# Zio_LiPo_Battery_Manager.net
KiCad netlist of a schematic drawn in EAGLE
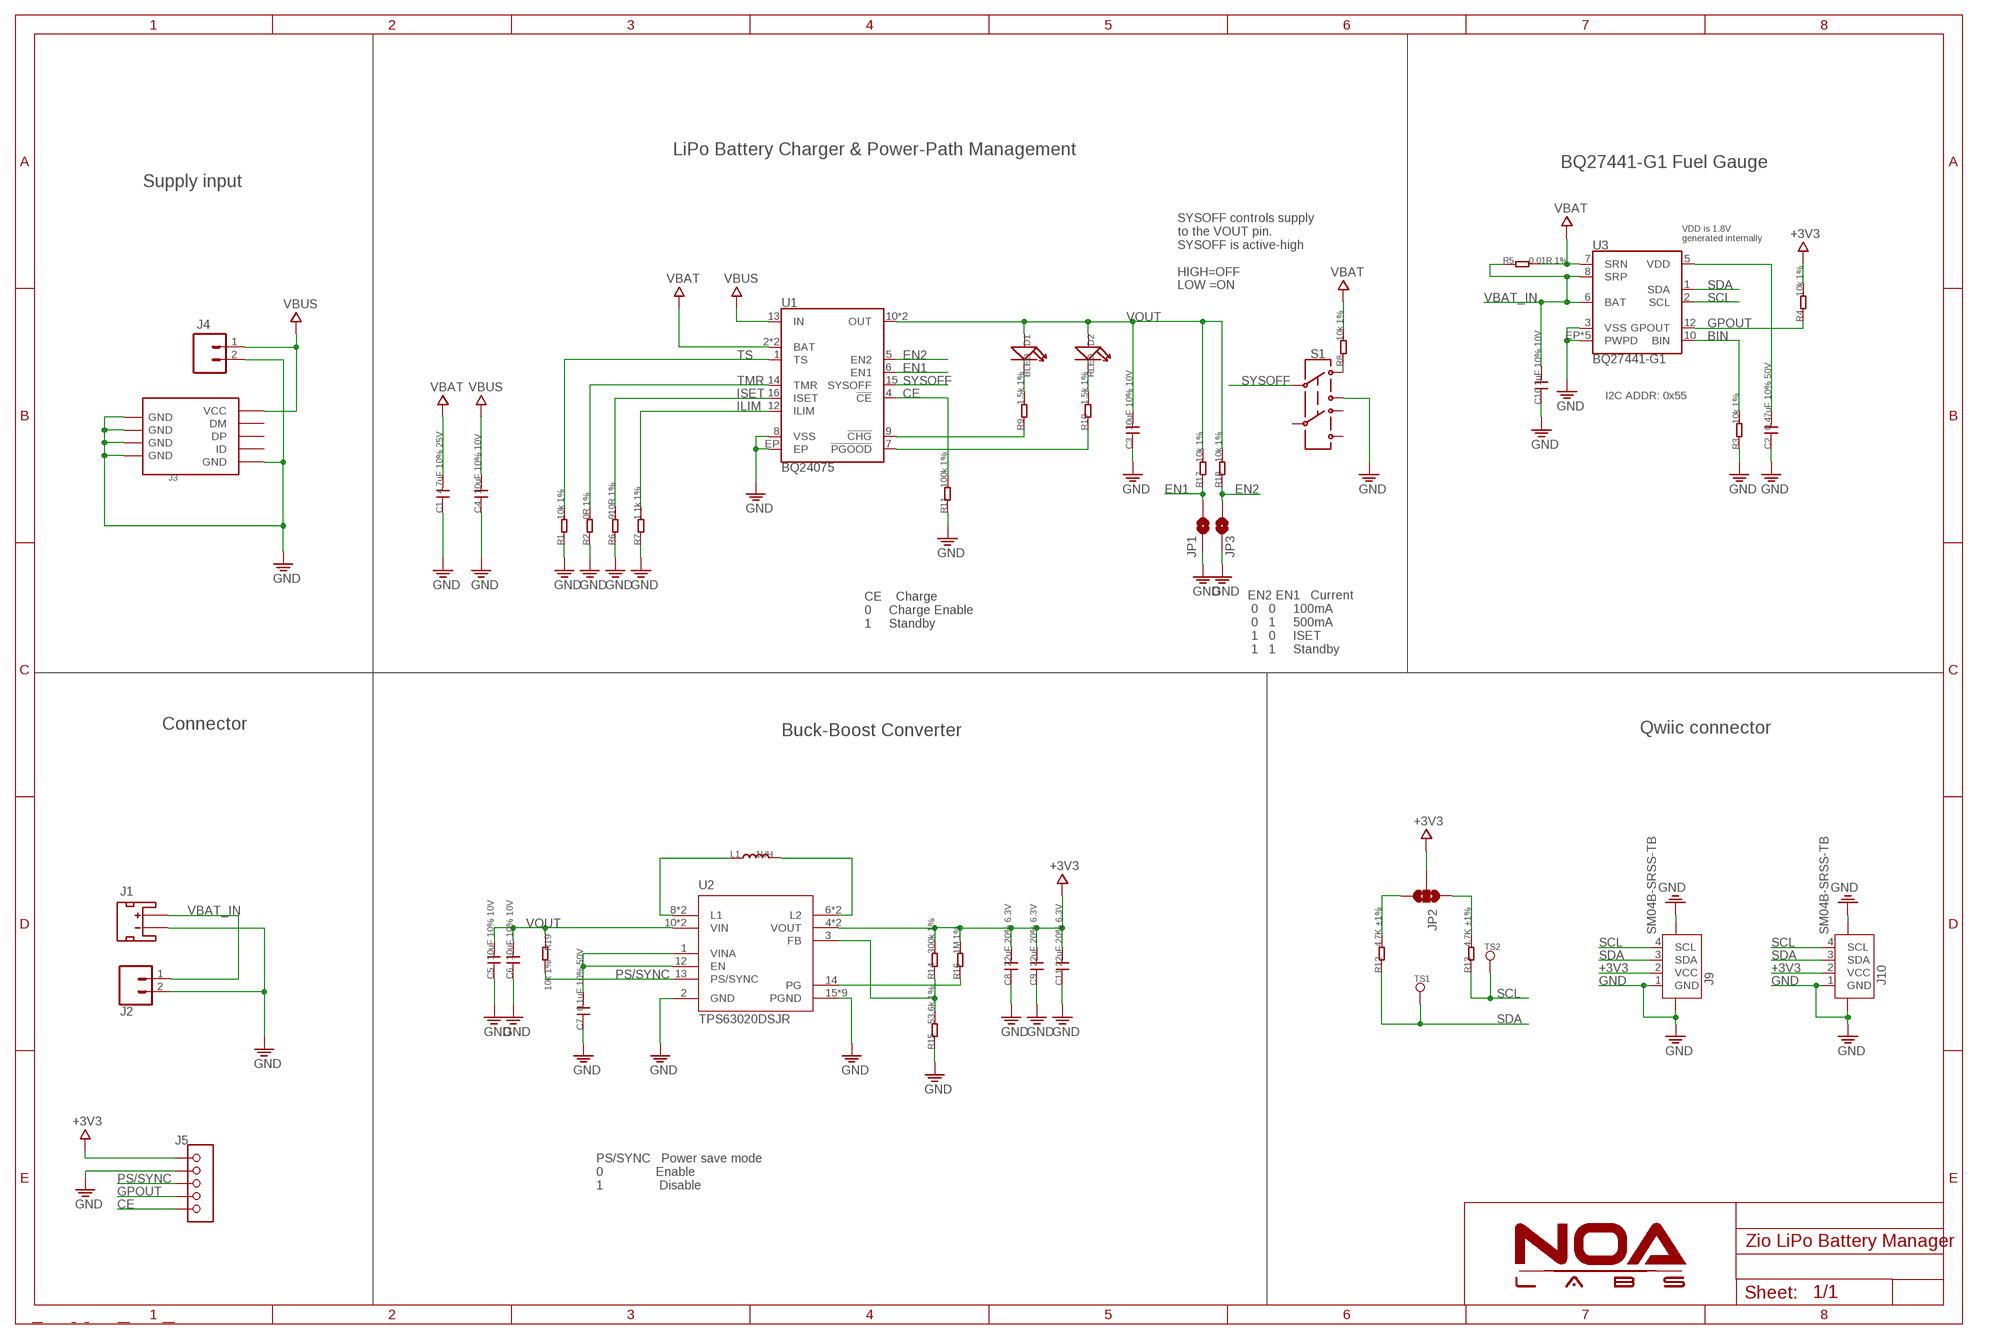
[diagram p0: schematic, sheet 1]

(export (version "E")
  (design (tool "Eeschema 10.0.6"))
  (components
    (comp (ref "C1")
      (value "4.7uF 10% 25V")
      (footprint "eagle-import:0603")
      (libsource (lib "eagle-import") (part "C-0603"))
    )
    (comp (ref "C2")
      (value "0.47uF 10% 50V")
      (footprint "eagle-import:0603")
      (libsource (lib "eagle-import") (part "C-0603"))
    )
    (comp (ref "C3")
      (value "10uF 10% 10V")
      (footprint "eagle-import:0805")
      (libsource (lib "eagle-import") (part "C-0805"))
    )
    (comp (ref "C4")
      (value "10uF 10% 10V")
      (footprint "eagle-import:0805")
      (libsource (lib "eagle-import") (part "C-0805"))
    )
    (comp (ref "C5")
      (value "10uF 10% 10V")
      (footprint "eagle-import:0805")
      (libsource (lib "eagle-import") (part "C-0805"))
    )
    (comp (ref "C6")
      (value "10uF 10% 10V")
      (footprint "eagle-import:0805")
      (libsource (lib "eagle-import") (part "C-0805"))
    )
    (comp (ref "C7")
      (value "0.1uF 10% 50V")
      (footprint "eagle-import:0603")
      (libsource (lib "eagle-import") (part "C-0603"))
    )
    (comp (ref "C8")
      (value "22uF 20% 6.3V")
      (footprint "eagle-import:0805")
      (libsource (lib "eagle-import") (part "C-0805"))
    )
    (comp (ref "C9")
      (value "22uF 20% 6.3V")
      (footprint "eagle-import:0805")
      (libsource (lib "eagle-import") (part "C-0805"))
    )
    (comp (ref "C10")
      (value "1uF 10% 10V")
      (footprint "eagle-import:0603")
      (libsource (lib "eagle-import") (part "C-0603"))
    )
    (comp (ref "C11")
      (value "22uF 20% 6.3V")
      (footprint "eagle-import:0805")
      (libsource (lib "eagle-import") (part "C-0805"))
    )
    (comp (ref "D1")
      (value "BLED")
      (footprint "eagle-import:LED-0603")
      (libsource (lib "eagle-import") (part "LED'0603'"))
    )
    (comp (ref "D2")
      (value "RLED")
      (footprint "eagle-import:LED-0603")
      (libsource (lib "eagle-import") (part "LED'0603'"))
    )
    (comp (ref "J1")
      (value "JST_2MM_MALE")
      (footprint "eagle-import:JST-2-SMD")
      (libsource (lib "eagle-import") (part "JST_2MM_MALE"))
    )
    (comp (ref "J2")
      (value "CONN_02")
      (footprint "eagle-import:1X02")
      (libsource (lib "eagle-import") (part "CONN_02"))
    )
    (comp (ref "J3")
      (value "USB-MICROE")
      (footprint "eagle-import:MICRO-SMD")
      (libsource (lib "eagle-import") (part "USB-MICROE"))
    )
    (comp (ref "J4")
      (value "CONN_02")
      (footprint "eagle-import:1X02")
      (libsource (lib "eagle-import") (part "CONN_02"))
    )
    (comp (ref "J5")
      (value "HEADER-5P-2.54")
      (footprint "eagle-import:5P-2.54")
      (libsource (lib "eagle-import") (part "HEADER-5P-2.54"))
    )
    (comp (ref "J9")
      (value "SM04B-SRSS-TB")
      (footprint "eagle-import:JST-SH-4P")
      (libsource (lib "eagle-import") (part "JST-SH-4P-1.0"))
    )
    (comp (ref "J10")
      (value "SM04B-SRSS-TB")
      (footprint "eagle-import:JST-SH-4P")
      (libsource (lib "eagle-import") (part "JST-SH-4P-1.0"))
    )
    (comp (ref "JP1")
      (value "JUMPER-SMT_2_NC_PASTE_NOCREM")
      (footprint "eagle-import:SMT-JUMPER_2_NC_PASTE_SILK_NOCREM")
      (libsource (lib "eagle-import") (part "JUMPER-SMT_2_NC_PASTE_NOCREM"))
    )
    (comp (ref "JP2")
      (value "JUMPER-SMT_3_2-NC_PASTE_NOCREM")
      (footprint "eagle-import:SMT-JUMPER_3_2-NC_PASTE_SILK_NOCREM")
      (libsource (lib "eagle-import") (part "JUMPER-SMT_3_2-NC_PASTE_NOCREM"))
    )
    (comp (ref "JP3")
      (value "JUMPER-SMT_2_NC_PASTE_NOCREM")
      (footprint "eagle-import:SMT-JUMPER_2_NC_PASTE_SILK_NOCREM")
      (libsource (lib "eagle-import") (part "JUMPER-SMT_2_NC_PASTE_NOCREM"))
    )
    (comp (ref "L1")
      (value "1UH")
      (footprint "eagle-import:0420M")
      (libsource (lib "eagle-import") (part "L-0420M"))
    )
    (comp (ref "R1")
      (value "10k 1%")
      (footprint "eagle-import:0603")
      (libsource (lib "eagle-import") (part "R-0603"))
    )
    (comp (ref "R2")
      (value "0R 1%")
      (footprint "eagle-import:0603")
      (libsource (lib "eagle-import") (part "R-0603"))
    )
    (comp (ref "R3")
      (value "10k 1%")
      (footprint "eagle-import:0603")
      (libsource (lib "eagle-import") (part "R-0603"))
    )
    (comp (ref "R4")
      (value "10k 1%")
      (footprint "eagle-import:0603")
      (libsource (lib "eagle-import") (part "R-0603"))
    )
    (comp (ref "R5")
      (value "0.01R 1%")
      (footprint "eagle-import:1206")
      (libsource (lib "eagle-import") (part "R-1206"))
    )
    (comp (ref "R6")
      (value "910R 1%")
      (footprint "eagle-import:0603")
      (libsource (lib "eagle-import") (part "R-0603"))
    )
    (comp (ref "R7")
      (value "1.1k 1%")
      (footprint "eagle-import:0603")
      (libsource (lib "eagle-import") (part "R-0603"))
    )
    (comp (ref "R8")
      (value "10k 1%")
      (footprint "eagle-import:0603")
      (libsource (lib "eagle-import") (part "R-0603"))
    )
    (comp (ref "R9")
      (value "1.5k 1%")
      (footprint "eagle-import:0603")
      (libsource (lib "eagle-import") (part "R-0603"))
    )
    (comp (ref "R10")
      (value "1.5k 1%")
      (footprint "eagle-import:0603")
      (libsource (lib "eagle-import") (part "R-0603"))
    )
    (comp (ref "R11")
      (value "100k 1%")
      (footprint "eagle-import:0603")
      (libsource (lib "eagle-import") (part "R-0603"))
    )
    (comp (ref "R12")
      (value "4.7K ±1%")
      (footprint "eagle-import:0603")
      (libsource (lib "eagle-import") (part "R-0603"))
    )
    (comp (ref "R13")
      (value "4.7K ±1%")
      (footprint "eagle-import:0603")
      (libsource (lib "eagle-import") (part "R-0603"))
    )
    (comp (ref "R14")
      (value "300k 1%")
      (footprint "eagle-import:0603")
      (libsource (lib "eagle-import") (part "R-0603"))
    )
    (comp (ref "R15")
      (value "53.6k 1%")
      (footprint "eagle-import:0603")
      (libsource (lib "eagle-import") (part "R-0603"))
    )
    (comp (ref "R16")
      (value "1M 1%")
      (footprint "eagle-import:0603")
      (libsource (lib "eagle-import") (part "R-0603"))
    )
    (comp (ref "R17")
      (value "10k 1%")
      (footprint "eagle-import:0603")
      (libsource (lib "eagle-import") (part "R-0603"))
    )
    (comp (ref "R18")
      (value "10k 1%")
      (footprint "eagle-import:0603")
      (libsource (lib "eagle-import") (part "R-0603"))
    )
    (comp (ref "R19")
      (value "10k 1%")
      (footprint "eagle-import:0603")
      (libsource (lib "eagle-import") (part "R-0603"))
    )
    (comp (ref "S1")
      (value "SWITCH-DPDT-SMD-AYZ0202")
      (footprint "eagle-import:SWITCH_DPDT_SMD_AYZ0202")
      (libsource (lib "eagle-import") (part "SWITCH-DPDT-SMD-AYZ0202"))
    )
    (comp (ref "TS1")
      (value "TEST_POINT35MIL")
      (footprint "eagle-import:1P-35MIL")
      (libsource (lib "eagle-import") (part "TEST_POINT35MIL"))
    )
    (comp (ref "TS2")
      (value "TEST_POINT35MIL")
      (footprint "eagle-import:1P-35MIL")
      (libsource (lib "eagle-import") (part "TEST_POINT35MIL"))
    )
    (comp (ref "U1")
      (value "BQ24075")
      (footprint "eagle-import:PVQFN-N16")
      (libsource (lib "eagle-import") (part "BQ24075"))
    )
    (comp (ref "U2")
      (value "TPS63020DSJR")
      (footprint "eagle-import:VSON-14")
      (libsource (lib "eagle-import") (part "TPS63020DSJR"))
    )
    (comp (ref "U3")
      (value "BQ27441-G1")
      (footprint "eagle-import:PDSO-N12")
      (libsource (lib "eagle-import") (part "BQ27441-G1"))
    )
  )
  (nets
    (net (code "1") (name "+3V3") (class "Default")
      (node (ref "C11") (pin "2") (pinfunction "2_2") (pintype "passive"))
      (node (ref "C8") (pin "2") (pinfunction "2_2") (pintype "passive"))
      (node (ref "C9") (pin "2") (pinfunction "2_2") (pintype "passive"))
      (node (ref "J10") (pin "2") (pinfunction "VCC_2") (pintype "bidirectional"))
      (node (ref "J5") (pin "1") (pinfunction "1_1") (pintype "bidirectional"))
      (node (ref "J9") (pin "2") (pinfunction "VCC_2") (pintype "bidirectional"))
      (node (ref "JP2") (pin "2") (pinfunction "2_2") (pintype "passive"))
      (node (ref "R14") (pin "2") (pinfunction "2_2") (pintype "passive"))
      (node (ref "R16") (pin "2") (pinfunction "2_2") (pintype "passive"))
      (node (ref "R4") (pin "2") (pinfunction "2_2") (pintype "passive"))
      (node (ref "U2") (pin "4") (pinfunction "VOUT_4") (pintype "bidirectional"))
      (node (ref "U2") (pin "5") (pinfunction "VOUT_5") (pintype "bidirectional"))
    )
    (net (code "2") (name "/BIN") (class "Default")
      (node (ref "R3") (pin "2") (pinfunction "2_2") (pintype "passive"))
      (node (ref "U3") (pin "10") (pinfunction "BIN_10") (pintype "bidirectional"))
    )
    (net (code "3") (name "/CE") (class "Default")
      (node (ref "J5") (pin "5") (pinfunction "5_5") (pintype "bidirectional"))
      (node (ref "R11") (pin "2") (pinfunction "2_2") (pintype "passive"))
      (node (ref "U1") (pin "4") (pinfunction "~{CE}_4") (pintype "bidirectional"))
    )
    (net (code "4") (name "/EN1") (class "Default")
      (node (ref "JP1") (pin "2") (pinfunction "2_2") (pintype "passive"))
      (node (ref "R17") (pin "1") (pinfunction "1_1") (pintype "passive"))
      (node (ref "U1") (pin "6") (pinfunction "EN1_6") (pintype "bidirectional"))
    )
    (net (code "5") (name "/EN2") (class "Default")
      (node (ref "JP3") (pin "2") (pinfunction "2_2") (pintype "passive"))
      (node (ref "R18") (pin "1") (pinfunction "1_1") (pintype "passive"))
      (node (ref "U1") (pin "5") (pinfunction "EN2_5") (pintype "bidirectional"))
    )
    (net (code "6") (name "/GPOUT") (class "Default")
      (node (ref "J5") (pin "4") (pinfunction "4_4") (pintype "bidirectional"))
      (node (ref "R4") (pin "1") (pinfunction "1_1") (pintype "passive"))
      (node (ref "U3") (pin "12") (pinfunction "GPOUT_12") (pintype "bidirectional"))
    )
    (net (code "7") (name "/ILIM") (class "Default")
      (node (ref "R7") (pin "2") (pinfunction "2_2") (pintype "passive"))
      (node (ref "U1") (pin "12") (pinfunction "ILIM_12") (pintype "bidirectional"))
    )
    (net (code "8") (name "/ISET") (class "Default")
      (node (ref "R6") (pin "2") (pinfunction "2_2") (pintype "passive"))
      (node (ref "U1") (pin "16") (pinfunction "ISET_16") (pintype "bidirectional"))
    )
    (net (code "9") (name "/PS{slash}SYNC") (class "Default")
      (node (ref "J5") (pin "3") (pinfunction "3_3") (pintype "bidirectional"))
      (node (ref "R19") (pin "2") (pinfunction "2_2") (pintype "passive"))
      (node (ref "U2") (pin "13") (pinfunction "PS/SYNC_13") (pintype "bidirectional"))
    )
    (net (code "10") (name "/SCL") (class "Default")
      (node (ref "J10") (pin "4") (pinfunction "SCL_4") (pintype "bidirectional"))
      (node (ref "J9") (pin "4") (pinfunction "SCL_4") (pintype "bidirectional"))
      (node (ref "R13") (pin "1") (pinfunction "1_1") (pintype "passive"))
      (node (ref "TS2") (pin "P$1") (pinfunction "1_P$1") (pintype "bidirectional"))
      (node (ref "U3") (pin "2") (pinfunction "SCL_2") (pintype "bidirectional"))
    )
    (net (code "11") (name "/SDA") (class "Default")
      (node (ref "J10") (pin "3") (pinfunction "SDA_3") (pintype "bidirectional"))
      (node (ref "J9") (pin "3") (pinfunction "SDA_3") (pintype "bidirectional"))
      (node (ref "R12") (pin "1") (pinfunction "1_1") (pintype "passive"))
      (node (ref "TS1") (pin "P$1") (pinfunction "1_P$1") (pintype "bidirectional"))
      (node (ref "U3") (pin "1") (pinfunction "SDA_1") (pintype "bidirectional"))
    )
    (net (code "12") (name "/SYSOFF") (class "Default")
      (node (ref "S1") (pin "2") (pinfunction "2_2") (pintype "bidirectional"))
      (node (ref "U1") (pin "15") (pinfunction "SYSOFF_15") (pintype "bidirectional"))
    )
    (net (code "13") (name "/TMR") (class "Default")
      (node (ref "R2") (pin "2") (pinfunction "2_2") (pintype "passive"))
      (node (ref "U1") (pin "14") (pinfunction "TMR_14") (pintype "bidirectional"))
    )
    (net (code "14") (name "/TS") (class "Default")
      (node (ref "R1") (pin "2") (pinfunction "2_2") (pintype "passive"))
      (node (ref "U1") (pin "1") (pinfunction "TS_1") (pintype "bidirectional"))
    )
    (net (code "15") (name "/VBAT_IN") (class "Default")
      (node (ref "C10") (pin "2") (pinfunction "2_2") (pintype "passive"))
      (node (ref "J1") (pin "2") (pinfunction "+_2") (pintype "bidirectional"))
      (node (ref "J2") (pin "1") (pinfunction "1_1") (pintype "passive"))
      (node (ref "R5") (pin "1") (pinfunction "1_1") (pintype "passive"))
      (node (ref "U3") (pin "6") (pinfunction "BAT_6") (pintype "bidirectional"))
      (node (ref "U3") (pin "8") (pinfunction "SRP_8") (pintype "bidirectional"))
    )
    (net (code "16") (name "/VOUT") (class "Default")
      (node (ref "C3") (pin "2") (pinfunction "2_2") (pintype "passive"))
      (node (ref "C5") (pin "2") (pinfunction "2_2") (pintype "passive"))
      (node (ref "C6") (pin "2") (pinfunction "2_2") (pintype "passive"))
      (node (ref "D1") (pin "+") (pinfunction "+_+") (pintype "passive"))
      (node (ref "D2") (pin "+") (pinfunction "+_+") (pintype "passive"))
      (node (ref "R17") (pin "2") (pinfunction "2_2") (pintype "passive"))
      (node (ref "R18") (pin "2") (pinfunction "2_2") (pintype "passive"))
      (node (ref "R19") (pin "1") (pinfunction "1_1") (pintype "passive"))
      (node (ref "U1") (pin "10") (pinfunction "OUT_10") (pintype "bidirectional"))
      (node (ref "U1") (pin "11") (pinfunction "OUT_11") (pintype "bidirectional"))
      (node (ref "U2") (pin "10") (pinfunction "VIN_10") (pintype "bidirectional"))
      (node (ref "U2") (pin "11") (pinfunction "VIN_11") (pintype "bidirectional"))
    )
    (net (code "17") (name "GND") (class "Default")
      (node (ref "C1") (pin "1") (pinfunction "1_1") (pintype "passive"))
      (node (ref "C10") (pin "1") (pinfunction "1_1") (pintype "passive"))
      (node (ref "C11") (pin "1") (pinfunction "1_1") (pintype "passive"))
      (node (ref "C2") (pin "1") (pinfunction "1_1") (pintype "passive"))
      (node (ref "C3") (pin "1") (pinfunction "1_1") (pintype "passive"))
      (node (ref "C4") (pin "1") (pinfunction "1_1") (pintype "passive"))
      (node (ref "C5") (pin "1") (pinfunction "1_1") (pintype "passive"))
      (node (ref "C6") (pin "1") (pinfunction "1_1") (pintype "passive"))
      (node (ref "C7") (pin "1") (pinfunction "1_1") (pintype "passive"))
      (node (ref "C8") (pin "1") (pinfunction "1_1") (pintype "passive"))
      (node (ref "C9") (pin "1") (pinfunction "1_1") (pintype "passive"))
      (node (ref "J1") (pin "1") (pinfunction "-_1") (pintype "bidirectional"))
      (node (ref "J10") (pin "1") (pinfunction "GND_1") (pintype "bidirectional"))
      (node (ref "J10") (pin "NC1") (pinfunction "5_NC1") (pintype "bidirectional"))
      (node (ref "J10") (pin "NC2") (pinfunction "6_NC2") (pintype "bidirectional"))
      (node (ref "J2") (pin "2") (pinfunction "2_2") (pintype "passive"))
      (node (ref "J3") (pin "GND") (pinfunction "GND_GND") (pintype "bidirectional"))
      (node (ref "J3") (pin "S1") (pinfunction "GND_S1") (pintype "bidirectional"))
      (node (ref "J3") (pin "S1@1") (pinfunction "GND_S1@1") (pintype "bidirectional"))
      (node (ref "J3") (pin "S1@2") (pinfunction "GND_S1@2") (pintype "bidirectional"))
      (node (ref "J3") (pin "S2") (pinfunction "GND_S2") (pintype "bidirectional"))
      (node (ref "J3") (pin "S2@1") (pinfunction "GND_S2@1") (pintype "bidirectional"))
      (node (ref "J3") (pin "S2@2") (pinfunction "GND_S2@2") (pintype "bidirectional"))
      (node (ref "J3") (pin "S3") (pinfunction "GND_S3") (pintype "bidirectional"))
      (node (ref "J3") (pin "S3@1") (pinfunction "GND_S3@1") (pintype "bidirectional"))
      (node (ref "J3") (pin "S3@2") (pinfunction "GND_S3@2") (pintype "bidirectional"))
      (node (ref "J3") (pin "S4") (pinfunction "GND_S4") (pintype "bidirectional"))
      (node (ref "J3") (pin "S4@1") (pinfunction "GND_S4@1") (pintype "bidirectional"))
      (node (ref "J3") (pin "S4@2") (pinfunction "GND_S4@2") (pintype "bidirectional"))
      (node (ref "J4") (pin "2") (pinfunction "2_2") (pintype "passive"))
      (node (ref "J5") (pin "2") (pinfunction "2_2") (pintype "bidirectional"))
      (node (ref "J9") (pin "1") (pinfunction "GND_1") (pintype "bidirectional"))
      (node (ref "J9") (pin "NC1") (pinfunction "5_NC1") (pintype "bidirectional"))
      (node (ref "J9") (pin "NC2") (pinfunction "6_NC2") (pintype "bidirectional"))
      (node (ref "JP1") (pin "1") (pinfunction "1_1") (pintype "passive"))
      (node (ref "JP3") (pin "1") (pinfunction "1_1") (pintype "passive"))
      (node (ref "R1") (pin "1") (pinfunction "1_1") (pintype "passive"))
      (node (ref "R11") (pin "1") (pinfunction "1_1") (pintype "passive"))
      (node (ref "R15") (pin "1") (pinfunction "1_1") (pintype "passive"))
      (node (ref "R2") (pin "1") (pinfunction "1_1") (pintype "passive"))
      (node (ref "R3") (pin "1") (pinfunction "1_1") (pintype "passive"))
      (node (ref "R6") (pin "1") (pinfunction "1_1") (pintype "passive"))
      (node (ref "R7") (pin "1") (pinfunction "1_1") (pintype "passive"))
      (node (ref "S1") (pin "3") (pinfunction "3_3") (pintype "bidirectional"))
      (node (ref "U1") (pin "8") (pinfunction "VSS_8") (pintype "bidirectional"))
      (node (ref "U1") (pin "EP") (pinfunction "EP_EP") (pintype "bidirectional"))
      (node (ref "U2") (pin "15") (pinfunction "PGND_15") (pintype "bidirectional"))
      (node (ref "U2") (pin "16") (pinfunction "PGND_16") (pintype "bidirectional"))
      (node (ref "U2") (pin "17") (pinfunction "PGND_17") (pintype "bidirectional"))
      (node (ref "U2") (pin "18") (pinfunction "PGND_18") (pintype "bidirectional"))
      (node (ref "U2") (pin "19") (pinfunction "PGND_19") (pintype "bidirectional"))
      (node (ref "U2") (pin "2") (pinfunction "GND_2") (pintype "bidirectional"))
      (node (ref "U2") (pin "20") (pinfunction "PGND_20") (pintype "bidirectional"))
      (node (ref "U2") (pin "21") (pinfunction "PGND_21") (pintype "bidirectional"))
      (node (ref "U2") (pin "22") (pinfunction "PGND_22") (pintype "bidirectional"))
      (node (ref "U2") (pin "23") (pinfunction "PGND_23") (pintype "bidirectional"))
      (node (ref "U3") (pin "3") (pinfunction "VSS_3") (pintype "bidirectional"))
      (node (ref "U3") (pin "EP") (pinfunction "PWPD_EP") (pintype "bidirectional"))
      (node (ref "U3") (pin "EP1") (pinfunction "PWPD_EP1") (pintype "bidirectional"))
      (node (ref "U3") (pin "EP2") (pinfunction "PWPD_EP2") (pintype "bidirectional"))
      (node (ref "U3") (pin "EP3") (pinfunction "PWPD_EP3") (pintype "bidirectional"))
      (node (ref "U3") (pin "EP4") (pinfunction "PWPD_EP4") (pintype "bidirectional"))
    )
    (net (code "18") (name "Net-(D1-Pad-)") (class "Default")
      (node (ref "D1") (pin "-") (pinfunction "-_-") (pintype "passive"))
      (node (ref "R9") (pin "2") (pinfunction "2_2") (pintype "passive"))
    )
    (net (code "19") (name "Net-(D2-Pad-)") (class "Default")
      (node (ref "D2") (pin "-") (pinfunction "-_-") (pintype "passive"))
      (node (ref "R10") (pin "2") (pinfunction "2_2") (pintype "passive"))
    )
    (net (code "20") (name "Net-(JP2-Pad1)") (class "Default")
      (node (ref "JP2") (pin "1") (pinfunction "1_1") (pintype "passive"))
      (node (ref "R13") (pin "2") (pinfunction "2_2") (pintype "passive"))
    )
    (net (code "21") (name "Net-(JP2-Pad3)") (class "Default")
      (node (ref "JP2") (pin "3") (pinfunction "3_3") (pintype "passive"))
      (node (ref "R12") (pin "2") (pinfunction "2_2") (pintype "passive"))
    )
    (net (code "22") (name "Net-(L1-Pad1)") (class "Default")
      (node (ref "L1") (pin "1") (pinfunction "1_1") (pintype "passive"))
      (node (ref "U2") (pin "8") (pinfunction "L1_8") (pintype "bidirectional"))
      (node (ref "U2") (pin "9") (pinfunction "L1_9") (pintype "bidirectional"))
    )
    (net (code "23") (name "Net-(L1-Pad2)") (class "Default")
      (node (ref "L1") (pin "2") (pinfunction "2_2") (pintype "passive"))
      (node (ref "U2") (pin "6") (pinfunction "L2_6") (pintype "bidirectional"))
      (node (ref "U2") (pin "7") (pinfunction "L2_7") (pintype "bidirectional"))
    )
    (net (code "24") (name "Net-(R8-Pad1)") (class "Default")
      (node (ref "R8") (pin "1") (pinfunction "1_1") (pintype "passive"))
      (node (ref "S1") (pin "1") (pinfunction "1_1") (pintype "bidirectional"))
    )
    (net (code "25") (name "Net-(U1-~{CHG})") (class "Default")
      (node (ref "R9") (pin "1") (pinfunction "1_1") (pintype "passive"))
      (node (ref "U1") (pin "9") (pinfunction "~{CHG}_9") (pintype "bidirectional"))
    )
    (net (code "26") (name "Net-(U1-~{PGOOD})") (class "Default")
      (node (ref "R10") (pin "1") (pinfunction "1_1") (pintype "passive"))
      (node (ref "U1") (pin "7") (pinfunction "~{PGOOD}_7") (pintype "bidirectional"))
    )
    (net (code "27") (name "Net-(U2-EN)") (class "Default")
      (node (ref "C7") (pin "2") (pinfunction "2_2") (pintype "passive"))
      (node (ref "U2") (pin "1") (pinfunction "VINA_1") (pintype "bidirectional"))
      (node (ref "U2") (pin "12") (pinfunction "EN_12") (pintype "bidirectional"))
    )
    (net (code "28") (name "Net-(U2-FB)") (class "Default")
      (node (ref "R14") (pin "1") (pinfunction "1_1") (pintype "passive"))
      (node (ref "R15") (pin "2") (pinfunction "2_2") (pintype "passive"))
      (node (ref "U2") (pin "3") (pinfunction "FB_3") (pintype "bidirectional"))
    )
    (net (code "29") (name "Net-(U2-PG)") (class "Default")
      (node (ref "R16") (pin "1") (pinfunction "1_1") (pintype "passive"))
      (node (ref "U2") (pin "14") (pinfunction "PG_14") (pintype "bidirectional"))
    )
    (net (code "30") (name "Net-(U3-VDD)") (class "Default")
      (node (ref "C2") (pin "2") (pinfunction "2_2") (pintype "passive"))
      (node (ref "U3") (pin "5") (pinfunction "VDD_5") (pintype "bidirectional"))
    )
    (net (code "31") (name "VBAT") (class "Default")
      (node (ref "C1") (pin "2") (pinfunction "2_2") (pintype "passive"))
      (node (ref "R5") (pin "2") (pinfunction "2_2") (pintype "passive"))
      (node (ref "R8") (pin "2") (pinfunction "2_2") (pintype "passive"))
      (node (ref "U1") (pin "2") (pinfunction "BAT_2") (pintype "bidirectional"))
      (node (ref "U1") (pin "3") (pinfunction "BAT_3") (pintype "bidirectional"))
      (node (ref "U3") (pin "7") (pinfunction "SRN_7") (pintype "bidirectional"))
    )
    (net (code "32") (name "VBUS") (class "Default")
      (node (ref "C4") (pin "2") (pinfunction "2_2") (pintype "passive"))
      (node (ref "J3") (pin "VBUS") (pinfunction "VCC_VBUS") (pintype "bidirectional"))
      (node (ref "J4") (pin "1") (pinfunction "1_1") (pintype "passive"))
      (node (ref "U1") (pin "13") (pinfunction "IN_13") (pintype "bidirectional"))
    )
    (net (code "33") (name "unconnected-(J1-PAD1-PadNC1)") (class "Default")
      (node (ref "J1") (pin "NC1") (pinfunction "PAD1_NC1") (pintype "bidirectional"))
    )
    (net (code "34") (name "unconnected-(J1-PAD2-PadNC2)") (class "Default")
      (node (ref "J1") (pin "NC2") (pinfunction "PAD2_NC2") (pintype "bidirectional"))
    )
    (net (code "35") (name "unconnected-(J3-DM-PadD-)") (class "Default")
      (node (ref "J3") (pin "D-") (pinfunction "DM_D-") (pintype "bidirectional"))
    )
    (net (code "36") (name "unconnected-(J3-DP-PadD+)") (class "Default")
      (node (ref "J3") (pin "D+") (pinfunction "DP_D+") (pintype "bidirectional"))
    )
    (net (code "37") (name "unconnected-(J3-PadID)") (class "Default")
      (node (ref "J3") (pin "ID") (pinfunction "ID_ID") (pintype "bidirectional"))
    )
    (net (code "38") (name "unconnected-(S1-Pad4)") (class "Default")
      (node (ref "S1") (pin "4") (pinfunction "4_4") (pintype "bidirectional"))
    )
    (net (code "39") (name "unconnected-(S1-Pad5)") (class "Default")
      (node (ref "S1") (pin "5") (pinfunction "5_5") (pintype "bidirectional"))
    )
    (net (code "40") (name "unconnected-(S1-Pad6)") (class "Default")
      (node (ref "S1") (pin "6") (pinfunction "6_6") (pintype "bidirectional"))
    )
  )
)
